# blink1mk2_v2cc.net
KiCad netlist of a schematic drawn in EAGLE
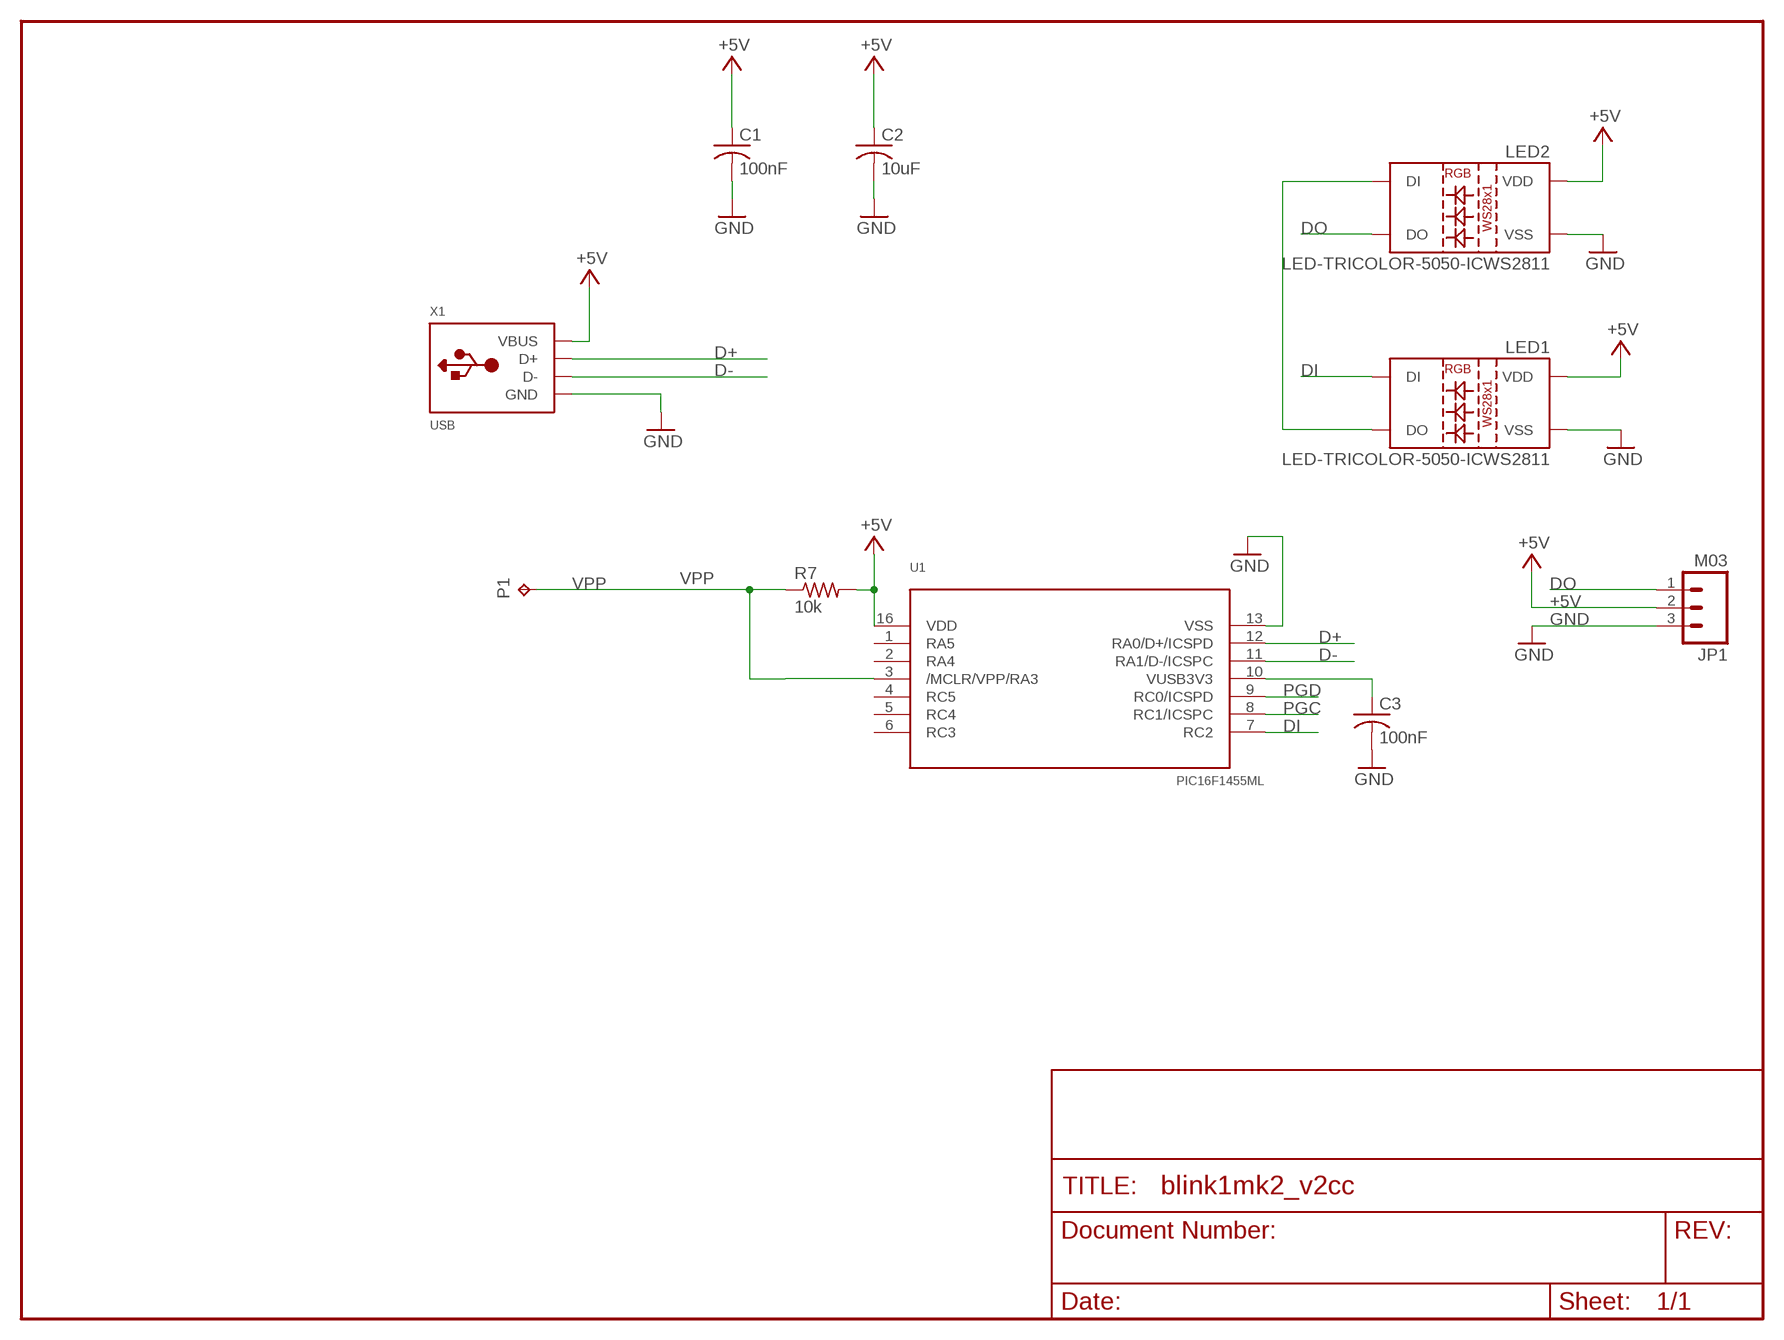
[diagram p0: schematic, sheet 1]

(export (version "E")
  (design (tool "Eeschema 10.0.6"))
  (components
    (comp (ref "C1")
      (value "100nF")
      (footprint "eagle-import:C0603")
      (libsource (lib "eagle-import") (part "C-USC0603"))
    )
    (comp (ref "C2")
      (value "10uF")
      (footprint "eagle-import:C0603")
      (libsource (lib "eagle-import") (part "C-USC0603"))
    )
    (comp (ref "C3")
      (value "100nF")
      (footprint "eagle-import:C0603")
      (libsource (lib "eagle-import") (part "C-USC0603"))
    )
    (comp (ref "JP1")
      (value "M03")
      (footprint "eagle-import:1X03-1.27MM")
      (libsource (lib "eagle-import") (part "M03"))
    )
    (comp (ref "LED1")
      (value "LED-TRICOLOR-5050-ICWS2811")
      (footprint "eagle-import:LED-TRICOLOR-5050-IC")
      (libsource (lib "eagle-import") (part "LED-TRICOLOR-5050-ICWS2811"))
    )
    (comp (ref "LED2")
      (value "LED-TRICOLOR-5050-ICWS2811")
      (footprint "eagle-import:LED-TRICOLOR-5050-IC")
      (libsource (lib "eagle-import") (part "LED-TRICOLOR-5050-ICWS2811"))
    )
    (comp (ref "P1")
      (value "TPTP11SQ")
      (footprint "eagle-import:TP11SQ")
      (libsource (lib "eagle-import") (part "TPTP11SQ"))
    )
    (comp (ref "R7")
      (value "10k")
      (footprint "eagle-import:R0603")
      (libsource (lib "eagle-import") (part "R-US_R0603"))
    )
    (comp (ref "U1")
      (value "PIC16F1455ML")
      (footprint "eagle-import:QFN16_4X4")
      (libsource (lib "eagle-import") (part "PIC16F1455ML"))
    )
    (comp (ref "X1")
      (value "USB")
      (footprint "eagle-import:MOLEX-48037-1000")
      (libsource (lib "eagle-import") (part "USB"))
    )
  )
  (nets
    (net (code "1") (name "+5V") (class "Default")
      (node (ref "C1") (pin "1") (pinfunction "1_1") (pintype "passive"))
      (node (ref "C2") (pin "1") (pinfunction "1_1") (pintype "passive"))
      (node (ref "JP1") (pin "2") (pinfunction "2_2") (pintype "passive"))
      (node (ref "LED1") (pin "3") (pinfunction "VDD_3") (pintype "bidirectional"))
      (node (ref "LED1") (pin "5") (pinfunction "VDD_5") (pintype "bidirectional"))
      (node (ref "LED2") (pin "3") (pinfunction "VDD_3") (pintype "bidirectional"))
      (node (ref "LED2") (pin "5") (pinfunction "VDD_5") (pintype "bidirectional"))
      (node (ref "R7") (pin "2") (pinfunction "2_2") (pintype "passive"))
      (node (ref "U1") (pin "16") (pinfunction "VDD_16") (pintype "bidirectional"))
      (node (ref "X1") (pin "1") (pinfunction "VBUS_1") (pintype "power_in"))
    )
    (net (code "2") (name "/D+") (class "Default")
      (node (ref "U1") (pin "12") (pinfunction "RA0/D+/ICSPD_12") (pintype "bidirectional"))
      (node (ref "X1") (pin "3") (pinfunction "D+_3") (pintype "bidirectional"))
    )
    (net (code "3") (name "/D-") (class "Default")
      (node (ref "U1") (pin "11") (pinfunction "RA1/D-/ICSPC_11") (pintype "bidirectional"))
      (node (ref "X1") (pin "2") (pinfunction "D-_2") (pintype "bidirectional"))
    )
    (net (code "4") (name "/DI") (class "Default")
      (node (ref "LED1") (pin "2") (pinfunction "DI_2") (pintype "bidirectional"))
      (node (ref "U1") (pin "7") (pinfunction "RC2_7") (pintype "bidirectional"))
    )
    (net (code "5") (name "/DO") (class "Default")
      (node (ref "JP1") (pin "1") (pinfunction "1_1") (pintype "passive"))
      (node (ref "LED2") (pin "1") (pinfunction "DO_1") (pintype "bidirectional"))
    )
    (net (code "6") (name "/PGC") (class "Default")
      (node (ref "U1") (pin "8") (pinfunction "RC1/ICSPC_8") (pintype "bidirectional"))
    )
    (net (code "7") (name "/PGD") (class "Default")
      (node (ref "U1") (pin "9") (pinfunction "RC0/ICSPD_9") (pintype "bidirectional"))
    )
    (net (code "8") (name "/VPP") (class "Default")
      (node (ref "P1") (pin "TP") (pinfunction "TP_TP") (pintype "input"))
      (node (ref "R7") (pin "1") (pinfunction "1_1") (pintype "passive"))
      (node (ref "U1") (pin "3") (pinfunction "/MCLR/VPP/RA3_3") (pintype "bidirectional"))
    )
    (net (code "9") (name "GND") (class "Default")
      (node (ref "C1") (pin "2") (pinfunction "2_2") (pintype "passive"))
      (node (ref "C2") (pin "2") (pinfunction "2_2") (pintype "passive"))
      (node (ref "C3") (pin "2") (pinfunction "2_2") (pintype "passive"))
      (node (ref "JP1") (pin "3") (pinfunction "3_3") (pintype "passive"))
      (node (ref "LED1") (pin "6") (pinfunction "VSS_6") (pintype "bidirectional"))
      (node (ref "LED2") (pin "6") (pinfunction "VSS_6") (pintype "bidirectional"))
      (node (ref "U1") (pin "13") (pinfunction "VSS_13") (pintype "bidirectional"))
      (node (ref "X1") (pin "4") (pinfunction "GND_4") (pintype "power_in"))
    )
    (net (code "10") (name "Net-(LED1-DO)") (class "Default")
      (node (ref "LED1") (pin "1") (pinfunction "DO_1") (pintype "bidirectional"))
      (node (ref "LED2") (pin "2") (pinfunction "DI_2") (pintype "bidirectional"))
    )
    (net (code "11") (name "Net-(U1-VUSB3V3)") (class "Default")
      (node (ref "C3") (pin "1") (pinfunction "1_1") (pintype "passive"))
      (node (ref "U1") (pin "10") (pinfunction "VUSB3V3_10") (pintype "bidirectional"))
    )
    (net (code "12") (name "unconnected-(U1-RA4-Pad2)") (class "Default")
      (node (ref "U1") (pin "2") (pinfunction "RA4_2") (pintype "bidirectional"))
    )
    (net (code "13") (name "unconnected-(U1-RA5-Pad1)") (class "Default")
      (node (ref "U1") (pin "1") (pinfunction "RA5_1") (pintype "bidirectional"))
    )
    (net (code "14") (name "unconnected-(U1-RC3-Pad6)") (class "Default")
      (node (ref "U1") (pin "6") (pinfunction "RC3_6") (pintype "bidirectional"))
    )
    (net (code "15") (name "unconnected-(U1-RC4-Pad5)") (class "Default")
      (node (ref "U1") (pin "5") (pinfunction "RC4_5") (pintype "bidirectional"))
    )
    (net (code "16") (name "unconnected-(U1-RC5-Pad4)") (class "Default")
      (node (ref "U1") (pin "4") (pinfunction "RC5_4") (pintype "bidirectional"))
    )
  )
)
